# ENC28j60_Ethernet.net
KiCad netlist of a schematic drawn in Altium Designer
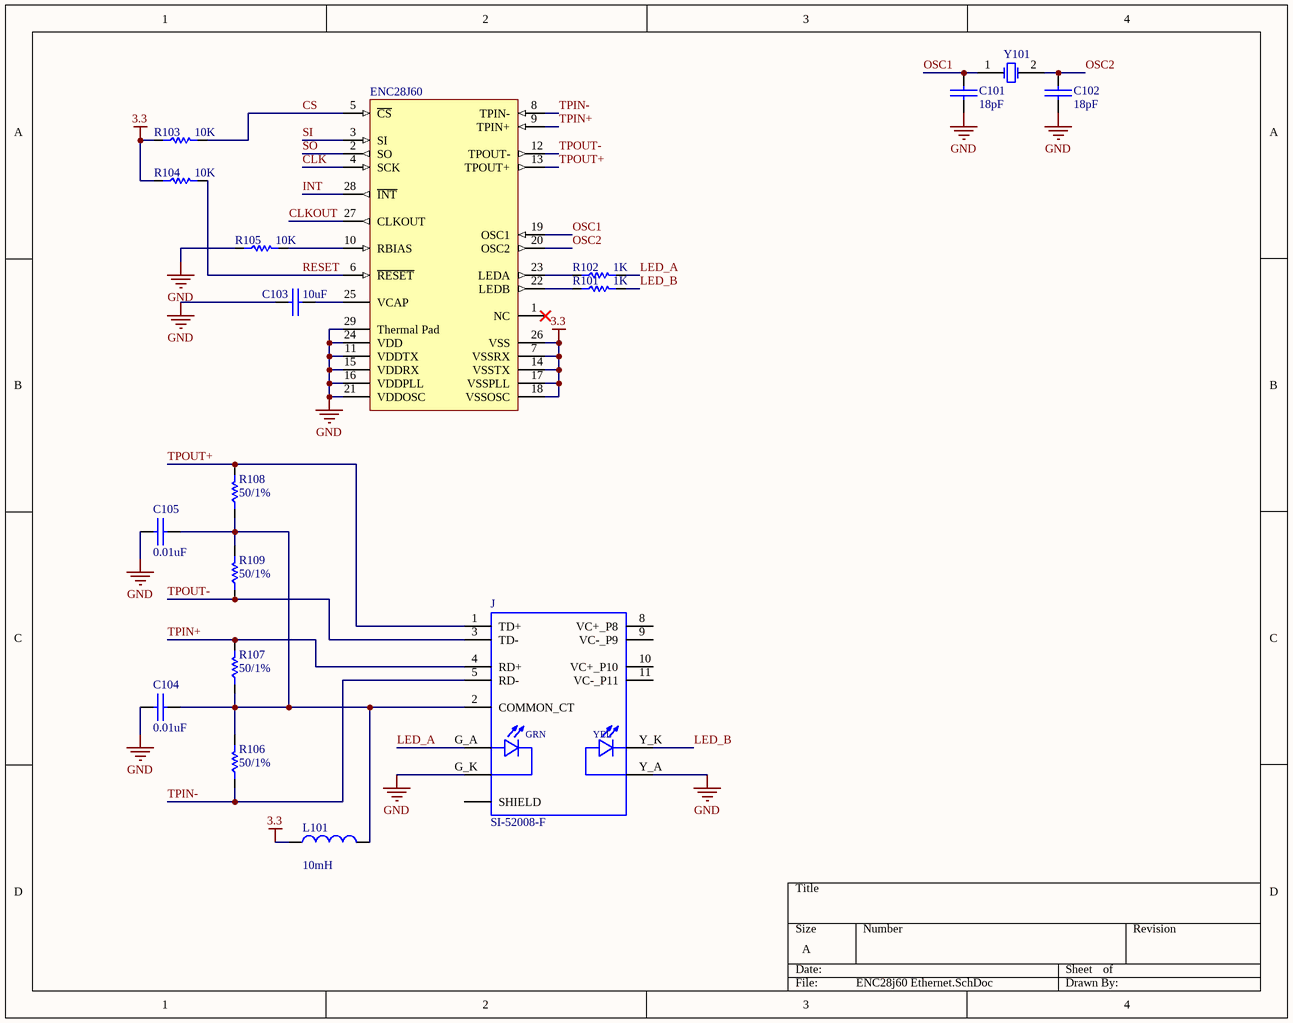
[diagram p0: ENC28j60 Ethernet.SchDoc]

(export (version "E")
  (design (tool "Eeschema 10.0.6"))
  (components
    (comp (ref "C101")
      (value "18pF")
      (footprint "SMD_CAP_0805")
      (description "Bipolar Capacitor")
      (fields (field (name "VOLTAGE") "100V") (field (name "DESIGNER") "Saeid Jorablo"))
      (libsource (lib "DDEms") (part "Cap-Bipolar"))
    )
    (comp (ref "C102")
      (value "18pF")
      (footprint "SMD_CAP_0805")
      (description "Bipolar Capacitor")
      (fields (field (name "VOLTAGE") "100V") (field (name "DESIGNER") "Saeid Jorablo"))
      (libsource (lib "DDEms") (part "Cap-Bipolar"))
    )
    (comp (ref "C103")
      (value "10uF")
      (footprint "SMD_CAP_0805")
      (description "Bipolar Capacitor")
      (fields (field (name "VOLTAGE") "100V") (field (name "DESIGNER") "Saeid Jorablo"))
      (libsource (lib "DDEms") (part "Cap-Bipolar"))
    )
    (comp (ref "C104")
      (value "0.01uF")
      (footprint "SMD_CAP_0805")
      (description "Bipolar Capacitor")
      (fields (field (name "VOLTAGE") "100V") (field (name "DESIGNER") "Saeid Jorablo"))
      (libsource (lib "DDEms") (part "Cap-Bipolar"))
    )
    (comp (ref "C105")
      (value "0.01uF")
      (footprint "SMD_CAP_0805")
      (description "Bipolar Capacitor")
      (fields (field (name "VOLTAGE") "100V") (field (name "DESIGNER") "Saeid Jorablo"))
      (libsource (lib "DDEms") (part "Cap-Bipolar"))
    )
    (comp (ref "ENC28J60")
      (value "ENC28J60/ML")
      (footprint "QFN-ML28_L")
      (description "Stand-Alone Ethernet Controller with SPI Interface, 28-Pin QFN")
      (fields (field (name "MANUFACTURER") "Microchip"))
      (libsource (lib "Interface_10 Microchip ") (part "ENC28J60/ML"))
    )
    (comp (ref "J")
      (value "SI-52008-F")
      (footprint "BEL_SI-52008-F")
      (description "1 Port RJ45 Magjack Connector Through Hole 10/100 Base-T, AutoMDIX, Power over Ethernet _PoE_")
      (fields (field (name "MF") "Stewart Connector"))
      (libsource (lib "SI-52008-F") (part "SI-52008-F"))
    )
    (comp (ref "L101")
      (value "10mH")
      (footprint "INDC1608L")
      (description "Inductor")
      (fields (field (name "PUBLISHER") "Altium Limited"))
      (libsource (lib "DDEms") (part "Inductor"))
    )
    (comp (ref "R101")
      (value "1K")
      (footprint "RES 0805 (2012X06L)")
      (description "Resistor")
      (fields (field (name "TOLERANCE") "5%") (field (name "POWER") "1/8 W"))
      (libsource (lib "DDEms") (part "Resistor"))
    )
    (comp (ref "R102")
      (value "1K")
      (footprint "RES 0805 (2012X06L)")
      (description "Resistor")
      (fields (field (name "TOLERANCE") "5%") (field (name "POWER") "1/8 W"))
      (libsource (lib "DDEms") (part "Resistor"))
    )
    (comp (ref "R103")
      (value "10K")
      (footprint "RES 0805 (2012X06L)")
      (description "Resistor")
      (fields (field (name "TOLERANCE") "5%") (field (name "POWER") "1/8 W"))
      (libsource (lib "DDEms") (part "Resistor"))
    )
    (comp (ref "R104")
      (value "10K")
      (footprint "RES 0805 (2012X06L)")
      (description "Resistor")
      (fields (field (name "TOLERANCE") "5%") (field (name "POWER") "1/8 W"))
      (libsource (lib "DDEms") (part "Resistor"))
    )
    (comp (ref "R105")
      (value "10K")
      (footprint "RES 0805 (2012X06L)")
      (description "Resistor")
      (fields (field (name "TOLERANCE") "5%") (field (name "POWER") "1/8 W"))
      (libsource (lib "DDEms") (part "Resistor"))
    )
    (comp (ref "R106")
      (value "50/1%")
      (footprint "RES 0805 (2012X06L)")
      (description "Resistor")
      (fields (field (name "TOLERANCE") "5%") (field (name "POWER") "1/8 W"))
      (libsource (lib "DDEms") (part "Resistor"))
    )
    (comp (ref "R107")
      (value "50/1%")
      (footprint "RES 0805 (2012X06L)")
      (description "Resistor")
      (fields (field (name "TOLERANCE") "5%") (field (name "POWER") "1/8 W"))
      (libsource (lib "DDEms") (part "Resistor"))
    )
    (comp (ref "R108")
      (value "50/1%")
      (footprint "RES 0805 (2012X06L)")
      (description "Resistor")
      (fields (field (name "TOLERANCE") "5%") (field (name "POWER") "1/8 W"))
      (libsource (lib "DDEms") (part "Resistor"))
    )
    (comp (ref "R109")
      (value "50/1%")
      (footprint "RES 0805 (2012X06L)")
      (description "Resistor")
      (fields (field (name "TOLERANCE") "5%") (field (name "POWER") "1/8 W"))
      (libsource (lib "DDEms") (part "Resistor"))
    )
    (comp (ref "Y101")
      (value "11.0592 MHz")
      (footprint "Crystal SMD")
      (description "XTAL Crystal")
      (libsource (lib "DDEms") (part "XTAL"))
    )
  )
  (nets
    (net (code "1") (name "/CLK") (class "Default")
      (node (ref "ENC28J60") (pin "4") (pinfunction "SCK_4") (pintype "input"))
    )
    (net (code "2") (name "/CLKOUT") (class "Default")
      (node (ref "ENC28J60") (pin "27") (pinfunction "CLKOUT_27") (pintype "output"))
    )
    (net (code "3") (name "/CS") (class "Default")
      (node (ref "ENC28J60") (pin "5") (pinfunction "~{CS}_5") (pintype "input"))
      (node (ref "R103") (pin "2") (pinfunction "2_2") (pintype "passive"))
    )
    (net (code "4") (name "/INT") (class "Default")
      (node (ref "ENC28J60") (pin "28") (pinfunction "~{INT}_28") (pintype "output"))
    )
    (net (code "5") (name "/LED_A") (class "Default")
      (node (ref "J") (pin "G_A") (pinfunction "G_A_G_A") (pintype "passive"))
      (node (ref "R102") (pin "2") (pinfunction "2_2") (pintype "passive"))
    )
    (net (code "6") (name "/LED_B") (class "Default")
      (node (ref "J") (pin "Y_K") (pinfunction "Y_K_Y_K") (pintype "passive"))
      (node (ref "R101") (pin "2") (pinfunction "2_2") (pintype "passive"))
    )
    (net (code "7") (name "/OSC1") (class "Default")
      (node (ref "C101") (pin "1") (pinfunction "+_1") (pintype "passive"))
      (node (ref "ENC28J60") (pin "19") (pinfunction "OSC1_19") (pintype "input"))
      (node (ref "Y101") (pin "1") (pinfunction "OSC1_1") (pintype "passive"))
    )
    (net (code "8") (name "/OSC2") (class "Default")
      (node (ref "C102") (pin "1") (pinfunction "+_1") (pintype "passive"))
      (node (ref "ENC28J60") (pin "20") (pinfunction "OSC2_20") (pintype "output"))
      (node (ref "Y101") (pin "2") (pinfunction "OSC2_2") (pintype "passive"))
    )
    (net (code "9") (name "/RESET") (class "Default")
      (node (ref "ENC28J60") (pin "6") (pinfunction "~{RESET}_6") (pintype "input"))
      (node (ref "R104") (pin "2") (pinfunction "2_2") (pintype "passive"))
    )
    (net (code "10") (name "/SI") (class "Default")
      (node (ref "ENC28J60") (pin "3") (pinfunction "SI_3") (pintype "input"))
    )
    (net (code "11") (name "/SO") (class "Default")
      (node (ref "ENC28J60") (pin "2") (pinfunction "SO_2") (pintype "output"))
    )
    (net (code "12") (name "/TPIN+") (class "Default")
      (node (ref "ENC28J60") (pin "9") (pinfunction "TPIN+_9") (pintype "input"))
      (node (ref "J") (pin "4") (pinfunction "RD+_4") (pintype "passive"))
      (node (ref "R107") (pin "2") (pinfunction "2_2") (pintype "passive"))
    )
    (net (code "13") (name "/TPIN-") (class "Default")
      (node (ref "ENC28J60") (pin "8") (pinfunction "TPIN-_8") (pintype "input"))
      (node (ref "J") (pin "5") (pinfunction "RD-_5") (pintype "passive"))
      (node (ref "R106") (pin "1") (pinfunction "1_1") (pintype "passive"))
    )
    (net (code "14") (name "/TPOUT+") (class "Default")
      (node (ref "ENC28J60") (pin "13") (pinfunction "TPOUT+_13") (pintype "output"))
      (node (ref "J") (pin "1") (pinfunction "TD+_1") (pintype "passive"))
      (node (ref "R108") (pin "2") (pinfunction "2_2") (pintype "passive"))
    )
    (net (code "15") (name "/TPOUT-") (class "Default")
      (node (ref "ENC28J60") (pin "12") (pinfunction "TPOUT-_12") (pintype "output"))
      (node (ref "J") (pin "3") (pinfunction "TD-_3") (pintype "passive"))
      (node (ref "R109") (pin "1") (pinfunction "1_1") (pintype "passive"))
    )
    (net (code "16") (name "3.3") (class "Default")
      (node (ref "ENC28J60") (pin "14") (pinfunction "VSSTX_14") (pintype "power_in"))
      (node (ref "ENC28J60") (pin "17") (pinfunction "VSSPLL_17") (pintype "power_in"))
      (node (ref "ENC28J60") (pin "18") (pinfunction "VSSOSC_18") (pintype "power_in"))
      (node (ref "ENC28J60") (pin "26") (pinfunction "VSS_26") (pintype "power_in"))
      (node (ref "ENC28J60") (pin "7") (pinfunction "VSSRX_7") (pintype "power_in"))
      (node (ref "L101") (pin "1") (pinfunction "1_1") (pintype "passive"))
      (node (ref "R103") (pin "1") (pinfunction "1_1") (pintype "passive"))
      (node (ref "R104") (pin "1") (pinfunction "1_1") (pintype "passive"))
    )
    (net (code "17") (name "GND") (class "Default")
      (node (ref "C101") (pin "2") (pinfunction "-_2") (pintype "passive"))
      (node (ref "C102") (pin "2") (pinfunction "-_2") (pintype "passive"))
      (node (ref "C103") (pin "1") (pinfunction "+_1") (pintype "passive"))
      (node (ref "C104") (pin "1") (pinfunction "+_1") (pintype "passive"))
      (node (ref "C105") (pin "1") (pinfunction "+_1") (pintype "passive"))
      (node (ref "ENC28J60") (pin "11") (pinfunction "VDDTX_11") (pintype "power_in"))
      (node (ref "ENC28J60") (pin "15") (pinfunction "VDDRX_15") (pintype "power_in"))
      (node (ref "ENC28J60") (pin "16") (pinfunction "VDDPLL_16") (pintype "power_in"))
      (node (ref "ENC28J60") (pin "21") (pinfunction "VDDOSC_21") (pintype "power_in"))
      (node (ref "ENC28J60") (pin "24") (pinfunction "VDD_24") (pintype "power_in"))
      (node (ref "ENC28J60") (pin "29") (pinfunction "Thermal_Pad_29") (pintype "passive"))
      (node (ref "J") (pin "G_K") (pinfunction "G_K_G_K") (pintype "passive"))
      (node (ref "J") (pin "Y_A") (pinfunction "Y_A_Y_A") (pintype "passive"))
      (node (ref "R105") (pin "1") (pinfunction "1_1") (pintype "passive"))
    )
    (net (code "18") (name "Net-(C103--)") (class "Default")
      (node (ref "C103") (pin "2") (pinfunction "-_2") (pintype "passive"))
      (node (ref "ENC28J60") (pin "25") (pinfunction "VCAP_25") (pintype "power_in"))
    )
    (net (code "19") (name "Net-(C104--)") (class "Default")
      (node (ref "C104") (pin "2") (pinfunction "-_2") (pintype "passive"))
      (node (ref "C105") (pin "2") (pinfunction "-_2") (pintype "passive"))
      (node (ref "J") (pin "2") (pinfunction "COMMON_CT_2") (pintype "passive"))
      (node (ref "L101") (pin "2") (pinfunction "2_2") (pintype "passive"))
      (node (ref "R106") (pin "2") (pinfunction "2_2") (pintype "passive"))
      (node (ref "R107") (pin "1") (pinfunction "1_1") (pintype "passive"))
      (node (ref "R108") (pin "1") (pinfunction "1_1") (pintype "passive"))
      (node (ref "R109") (pin "2") (pinfunction "2_2") (pintype "passive"))
    )
    (net (code "20") (name "Net-(ENC28J60-LEDA)") (class "Default")
      (node (ref "ENC28J60") (pin "23") (pinfunction "LEDA_23") (pintype "output"))
      (node (ref "R102") (pin "1") (pinfunction "1_1") (pintype "passive"))
    )
    (net (code "21") (name "Net-(ENC28J60-LEDB)") (class "Default")
      (node (ref "ENC28J60") (pin "22") (pinfunction "LEDB_22") (pintype "output"))
      (node (ref "R101") (pin "1") (pinfunction "1_1") (pintype "passive"))
    )
    (net (code "22") (name "Net-(ENC28J60-RBIAS)") (class "Default")
      (node (ref "ENC28J60") (pin "10") (pinfunction "RBIAS_10") (pintype "input"))
      (node (ref "R105") (pin "2") (pinfunction "2_2") (pintype "passive"))
    )
    (net (code "23") (name "Net-(J-SHIELD-PadS1)") (class "Default")
      (node (ref "J") (pin "S1") (pinfunction "SHIELD_S1") (pintype "passive"))
      (node (ref "J") (pin "S2") (pinfunction "SHIELD_S2") (pintype "passive"))
    )
    (net (code "24") (name "unconnected-(ENC28J60-NC-Pad1)") (class "Default")
      (node (ref "ENC28J60") (pin "1") (pinfunction "NC_1") (pintype "passive+no_connect"))
    )
    (net (code "25") (name "unconnected-(J-VC+_P8-Pad8)") (class "Default")
      (node (ref "J") (pin "8") (pinfunction "VC+_P8_8") (pintype "passive"))
    )
    (net (code "26") (name "unconnected-(J-VC+_P10-Pad10)") (class "Default")
      (node (ref "J") (pin "10") (pinfunction "VC+_P10_10") (pintype "passive"))
    )
    (net (code "27") (name "unconnected-(J-VC-_P9-Pad9)") (class "Default")
      (node (ref "J") (pin "9") (pinfunction "VC-_P9_9") (pintype "passive"))
    )
    (net (code "28") (name "unconnected-(J-VC-_P11-Pad11)") (class "Default")
      (node (ref "J") (pin "11") (pinfunction "VC-_P11_11") (pintype "passive"))
    )
  )
)
